# A4988_motor_drivers.net
KiCad netlist of a schematic drawn in Altium Designer
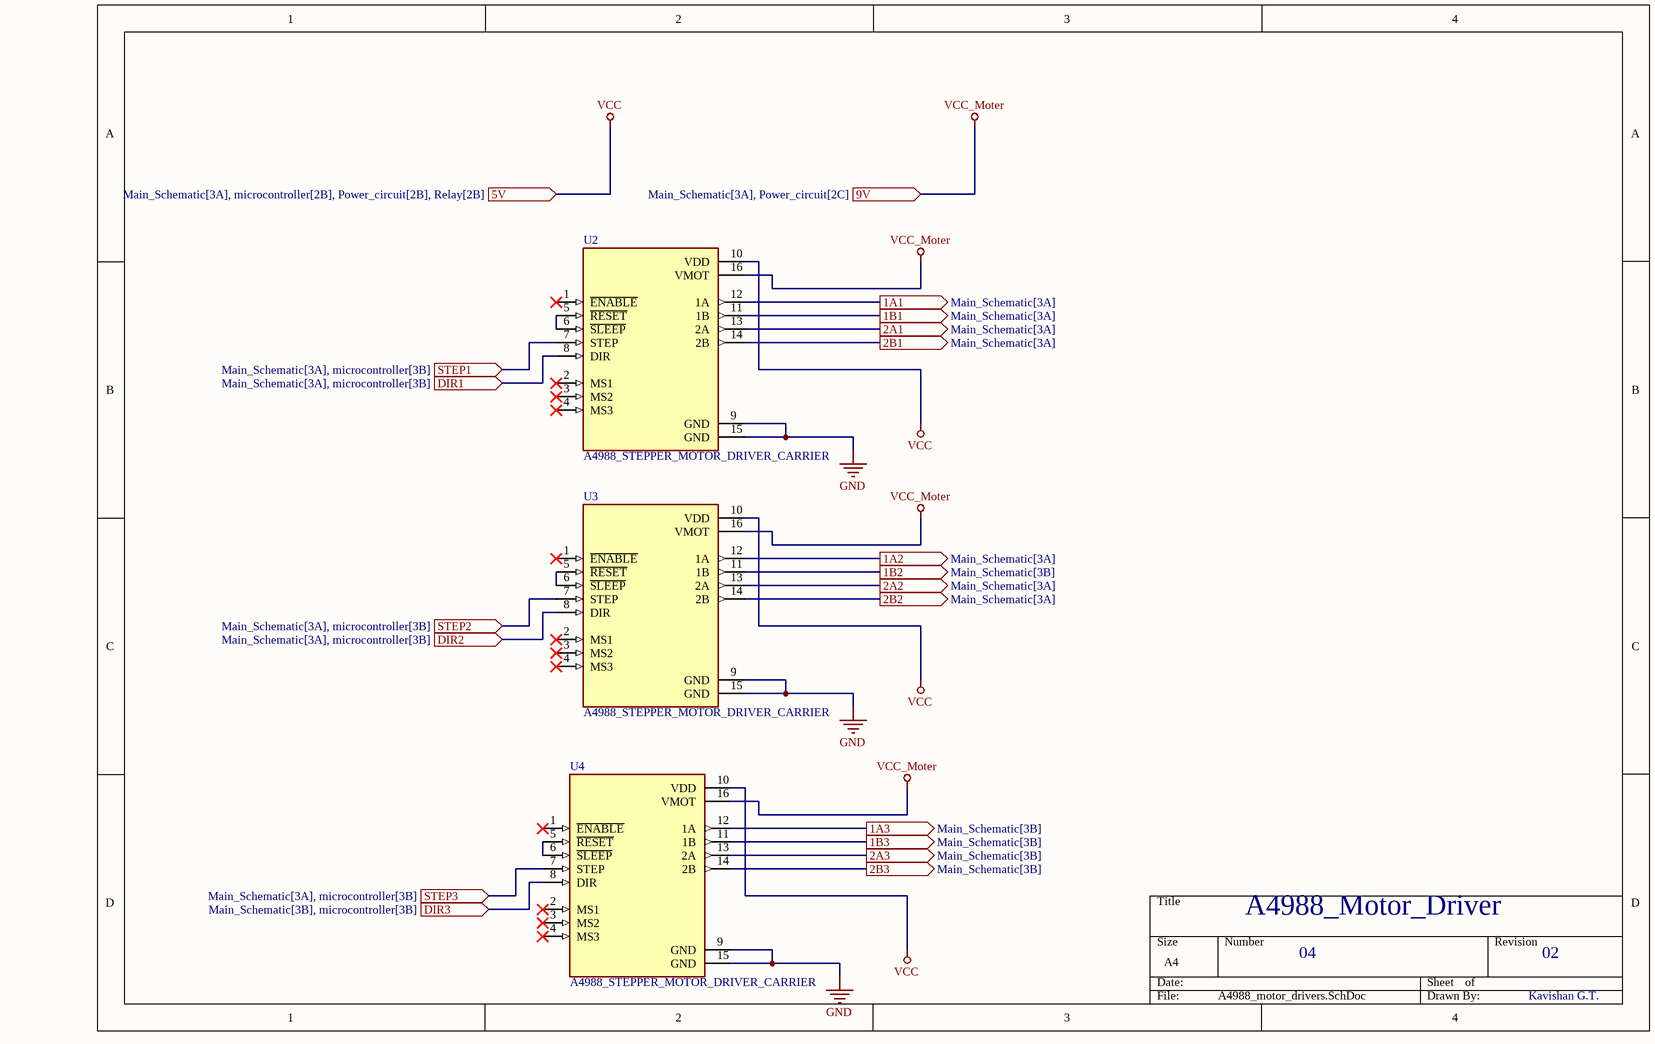
[diagram p0: A4988_motor_drivers.SchDoc]

(export (version "E")
  (design (tool "Eeschema 10.0.6"))
  (components
    (comp (ref "U2")
      (value "A4988_STEPPER_MOTOR_DRIVER_CARRIER")
      (footprint "MODULE_A4988_STEPPER_MOTOR_DRIVER_CARRIER")
      (description "Stepper motor controler; IC: A4988; 1A; Uin mot: 8Ã·35V")
      (libsource (lib "A4988_STEPPER_MOTOR_DRIVER_CARRIER") (part "A4988_STEPPER_MOTOR_DRIVER_CARRIER"))
    )
    (comp (ref "U3")
      (value "A4988_STEPPER_MOTOR_DRIVER_CARRIER")
      (footprint "MODULE_A4988_STEPPER_MOTOR_DRIVER_CARRIER")
      (description "Stepper motor controler; IC: A4988; 1A; Uin mot: 8Ã·35V")
      (libsource (lib "A4988_STEPPER_MOTOR_DRIVER_CARRIER") (part "A4988_STEPPER_MOTOR_DRIVER_CARRIER"))
    )
    (comp (ref "U4")
      (value "A4988_STEPPER_MOTOR_DRIVER_CARRIER")
      (footprint "MODULE_A4988_STEPPER_MOTOR_DRIVER_CARRIER")
      (description "Stepper motor controler; IC: A4988; 1A; Uin mot: 8Ã·35V")
      (libsource (lib "A4988_STEPPER_MOTOR_DRIVER_CARRIER") (part "A4988_STEPPER_MOTOR_DRIVER_CARRIER"))
    )
  )
  (nets
    (net (code "1") (name "/1A1") (class "Default")
      (node (ref "U2") (pin "12") (pinfunction "1A_12") (pintype "output"))
    )
    (net (code "2") (name "/1A2") (class "Default")
      (node (ref "U3") (pin "12") (pinfunction "1A_12") (pintype "output"))
    )
    (net (code "3") (name "/1A3") (class "Default")
      (node (ref "U4") (pin "12") (pinfunction "1A_12") (pintype "output"))
    )
    (net (code "4") (name "/1B1") (class "Default")
      (node (ref "U2") (pin "11") (pinfunction "1B_11") (pintype "output"))
    )
    (net (code "5") (name "/1B2") (class "Default")
      (node (ref "U3") (pin "11") (pinfunction "1B_11") (pintype "output"))
    )
    (net (code "6") (name "/1B3") (class "Default")
      (node (ref "U4") (pin "11") (pinfunction "1B_11") (pintype "output"))
    )
    (net (code "7") (name "/2A1") (class "Default")
      (node (ref "U2") (pin "13") (pinfunction "2A_13") (pintype "output"))
    )
    (net (code "8") (name "/2A2") (class "Default")
      (node (ref "U3") (pin "13") (pinfunction "2A_13") (pintype "output"))
    )
    (net (code "9") (name "/2A3") (class "Default")
      (node (ref "U4") (pin "13") (pinfunction "2A_13") (pintype "output"))
    )
    (net (code "10") (name "/2B1") (class "Default")
      (node (ref "U2") (pin "14") (pinfunction "2B_14") (pintype "output"))
    )
    (net (code "11") (name "/2B2") (class "Default")
      (node (ref "U3") (pin "14") (pinfunction "2B_14") (pintype "output"))
    )
    (net (code "12") (name "/2B3") (class "Default")
      (node (ref "U4") (pin "14") (pinfunction "2B_14") (pintype "output"))
    )
    (net (code "13") (name "/DIR1") (class "Default")
      (node (ref "U2") (pin "8") (pinfunction "DIR_8") (pintype "input"))
    )
    (net (code "14") (name "/DIR2") (class "Default")
      (node (ref "U3") (pin "8") (pinfunction "DIR_8") (pintype "input"))
    )
    (net (code "15") (name "/DIR3") (class "Default")
      (node (ref "U4") (pin "8") (pinfunction "DIR_8") (pintype "input"))
    )
    (net (code "16") (name "/STEP1") (class "Default")
      (node (ref "U2") (pin "7") (pinfunction "STEP_7") (pintype "input"))
    )
    (net (code "17") (name "/STEP2") (class "Default")
      (node (ref "U3") (pin "7") (pinfunction "STEP_7") (pintype "input"))
    )
    (net (code "18") (name "/STEP3") (class "Default")
      (node (ref "U4") (pin "7") (pinfunction "STEP_7") (pintype "input"))
    )
    (net (code "19") (name "GND") (class "Default")
      (node (ref "U2") (pin "15") (pinfunction "GND_15") (pintype "power_in"))
      (node (ref "U2") (pin "9") (pinfunction "GND_9") (pintype "power_in"))
      (node (ref "U3") (pin "15") (pinfunction "GND_15") (pintype "power_in"))
      (node (ref "U3") (pin "9") (pinfunction "GND_9") (pintype "power_in"))
      (node (ref "U4") (pin "15") (pinfunction "GND_15") (pintype "power_in"))
      (node (ref "U4") (pin "9") (pinfunction "GND_9") (pintype "power_in"))
    )
    (net (code "20") (name "Net-(U2-~{RESET})") (class "Default")
      (node (ref "U2") (pin "5") (pinfunction "~{RESET}_5") (pintype "input"))
      (node (ref "U2") (pin "6") (pinfunction "~{SLEEP}_6") (pintype "input"))
    )
    (net (code "21") (name "Net-(U3-~{RESET})") (class "Default")
      (node (ref "U3") (pin "5") (pinfunction "~{RESET}_5") (pintype "input"))
      (node (ref "U3") (pin "6") (pinfunction "~{SLEEP}_6") (pintype "input"))
    )
    (net (code "22") (name "Net-(U4-~{RESET})") (class "Default")
      (node (ref "U4") (pin "5") (pinfunction "~{RESET}_5") (pintype "input"))
      (node (ref "U4") (pin "6") (pinfunction "~{SLEEP}_6") (pintype "input"))
    )
    (net (code "23") (name "VCC") (class "Default")
      (node (ref "U2") (pin "10") (pinfunction "VDD_10") (pintype "power_in"))
      (node (ref "U3") (pin "10") (pinfunction "VDD_10") (pintype "power_in"))
      (node (ref "U4") (pin "10") (pinfunction "VDD_10") (pintype "power_in"))
    )
    (net (code "24") (name "VCC_Moter") (class "Default")
      (node (ref "U2") (pin "16") (pinfunction "VMOT_16") (pintype "power_in"))
      (node (ref "U3") (pin "16") (pinfunction "VMOT_16") (pintype "power_in"))
      (node (ref "U4") (pin "16") (pinfunction "VMOT_16") (pintype "power_in"))
    )
    (net (code "25") (name "unconnected-(U2-MS1-Pad2)") (class "Default")
      (node (ref "U2") (pin "2") (pinfunction "MS1_2") (pintype "input+no_connect"))
    )
    (net (code "26") (name "unconnected-(U2-MS2-Pad3)") (class "Default")
      (node (ref "U2") (pin "3") (pinfunction "MS2_3") (pintype "input+no_connect"))
    )
    (net (code "27") (name "unconnected-(U2-MS3-Pad4)") (class "Default")
      (node (ref "U2") (pin "4") (pinfunction "MS3_4") (pintype "input+no_connect"))
    )
    (net (code "28") (name "unconnected-(U2-~{ENABLE}-Pad1)") (class "Default")
      (node (ref "U2") (pin "1") (pinfunction "~{ENABLE}_1") (pintype "input+no_connect"))
    )
    (net (code "29") (name "unconnected-(U3-MS1-Pad2)") (class "Default")
      (node (ref "U3") (pin "2") (pinfunction "MS1_2") (pintype "input+no_connect"))
    )
    (net (code "30") (name "unconnected-(U3-MS2-Pad3)") (class "Default")
      (node (ref "U3") (pin "3") (pinfunction "MS2_3") (pintype "input+no_connect"))
    )
    (net (code "31") (name "unconnected-(U3-MS3-Pad4)") (class "Default")
      (node (ref "U3") (pin "4") (pinfunction "MS3_4") (pintype "input+no_connect"))
    )
    (net (code "32") (name "unconnected-(U3-~{ENABLE}-Pad1)") (class "Default")
      (node (ref "U3") (pin "1") (pinfunction "~{ENABLE}_1") (pintype "input+no_connect"))
    )
    (net (code "33") (name "unconnected-(U4-MS1-Pad2)") (class "Default")
      (node (ref "U4") (pin "2") (pinfunction "MS1_2") (pintype "input+no_connect"))
    )
    (net (code "34") (name "unconnected-(U4-MS2-Pad3)") (class "Default")
      (node (ref "U4") (pin "3") (pinfunction "MS2_3") (pintype "input+no_connect"))
    )
    (net (code "35") (name "unconnected-(U4-MS3-Pad4)") (class "Default")
      (node (ref "U4") (pin "4") (pinfunction "MS3_4") (pintype "input+no_connect"))
    )
    (net (code "36") (name "unconnected-(U4-~{ENABLE}-Pad1)") (class "Default")
      (node (ref "U4") (pin "1") (pinfunction "~{ENABLE}_1") (pintype "input+no_connect"))
    )
  )
)
